# module_SX1262.net
KiCad netlist of a schematic drawn in EAGLE
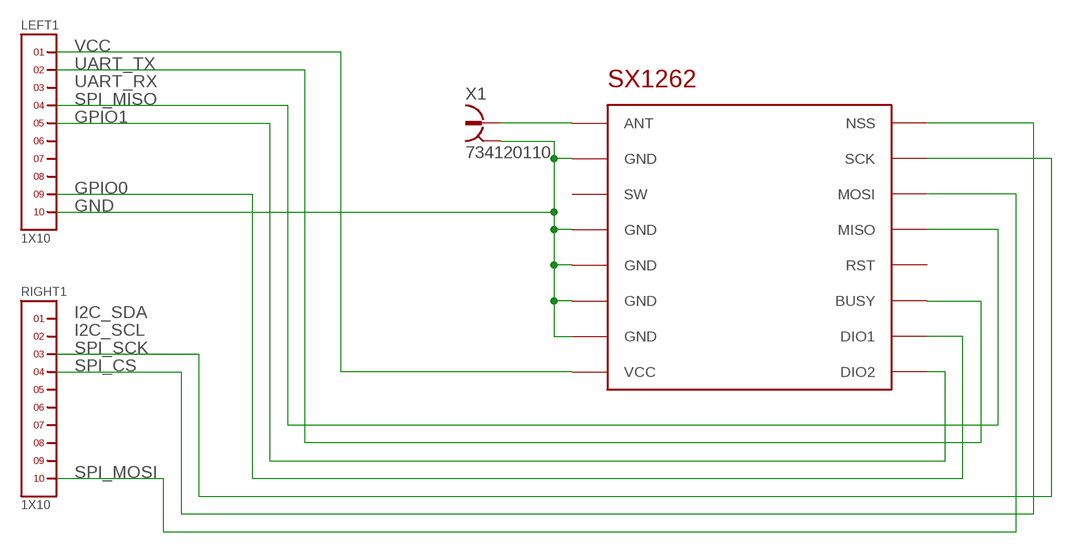
[diagram p0: schematic, sheet 1]

(export (version "E")
  (design (tool "Eeschema 10.0.6"))
  (components
    (comp (ref "LEFT1")
      (value "1X10")
      (footprint "eagle-import:1X10")
      (libsource (lib "eagle-import") (part "1X10"))
    )
    (comp (ref "RIGHT1")
      (value "1X10")
      (footprint "eagle-import:1X10")
      (libsource (lib "eagle-import") (part "1X10"))
    )
    (comp (ref "U$1")
      (value "SX1262")
      (footprint "eagle-import:SX1262")
      (libsource (lib "eagle-import") (part "SX1262"))
    )
    (comp (ref "X1")
      (value "734120110")
      (footprint "eagle-import:734120110")
      (libsource (lib "eagle-import") (part "734120110"))
    )
  )
  (nets
    (net (code "1") (name "Net-(LEFT1-Pad1)") (class "Default")
      (node (ref "LEFT1") (pin "1") (pinfunction "1_1") (pintype "bidirectional"))
      (node (ref "U$1") (pin "VCC") (pinfunction "VCC_VCC") (pintype "bidirectional"))
    )
    (net (code "2") (name "Net-(LEFT1-Pad2)") (class "Default")
      (node (ref "LEFT1") (pin "2") (pinfunction "2_2") (pintype "bidirectional"))
      (node (ref "U$1") (pin "BUSY") (pinfunction "BUSY_BUSY") (pintype "bidirectional"))
    )
    (net (code "3") (name "Net-(LEFT1-Pad4)") (class "Default")
      (node (ref "LEFT1") (pin "4") (pinfunction "4_4") (pintype "bidirectional"))
      (node (ref "U$1") (pin "MISO") (pinfunction "MISO_MISO") (pintype "bidirectional"))
    )
    (net (code "4") (name "Net-(LEFT1-Pad5)") (class "Default")
      (node (ref "LEFT1") (pin "5") (pinfunction "5_5") (pintype "bidirectional"))
      (node (ref "U$1") (pin "DIO2") (pinfunction "DIO2_DIO2") (pintype "bidirectional"))
    )
    (net (code "5") (name "Net-(LEFT1-Pad9)") (class "Default")
      (node (ref "LEFT1") (pin "9") (pinfunction "9_9") (pintype "bidirectional"))
      (node (ref "U$1") (pin "DIO1") (pinfunction "DIO1_DIO1") (pintype "bidirectional"))
    )
    (net (code "6") (name "Net-(LEFT1-Pad10)") (class "Default")
      (node (ref "LEFT1") (pin "10") (pinfunction "10_10") (pintype "bidirectional"))
      (node (ref "U$1") (pin "GND@1") (pinfunction "GND_GND@1") (pintype "bidirectional"))
      (node (ref "U$1") (pin "GND@2") (pinfunction "GND_GND@2") (pintype "bidirectional"))
      (node (ref "U$1") (pin "GND@3") (pinfunction "GND_GND@3") (pintype "bidirectional"))
      (node (ref "U$1") (pin "GND@4") (pinfunction "GND_GND@4") (pintype "bidirectional"))
      (node (ref "U$1") (pin "GND@5") (pinfunction "GND_GND@5") (pintype "bidirectional"))
      (node (ref "X1") (pin "S@1") (pinfunction "2_S@1") (pintype "passive"))
      (node (ref "X1") (pin "S@2") (pinfunction "2_S@2") (pintype "passive"))
      (node (ref "X1") (pin "S@3") (pinfunction "2_S@3") (pintype "passive"))
    )
    (net (code "7") (name "Net-(RIGHT1-Pad3)") (class "Default")
      (node (ref "RIGHT1") (pin "3") (pinfunction "3_3") (pintype "bidirectional"))
      (node (ref "U$1") (pin "SCK") (pinfunction "SCK_SCK") (pintype "bidirectional"))
    )
    (net (code "8") (name "Net-(RIGHT1-Pad4)") (class "Default")
      (node (ref "RIGHT1") (pin "4") (pinfunction "4_4") (pintype "bidirectional"))
      (node (ref "U$1") (pin "NSS") (pinfunction "NSS_NSS") (pintype "bidirectional"))
    )
    (net (code "9") (name "Net-(RIGHT1-Pad10)") (class "Default")
      (node (ref "RIGHT1") (pin "10") (pinfunction "10_10") (pintype "bidirectional"))
      (node (ref "U$1") (pin "MOSI") (pinfunction "MOSI_MOSI") (pintype "bidirectional"))
    )
    (net (code "10") (name "Net-(U$1-PadANT)") (class "Default")
      (node (ref "U$1") (pin "ANT") (pinfunction "ANT_ANT") (pintype "bidirectional"))
      (node (ref "X1") (pin "1") (pinfunction "1_1") (pintype "passive"))
    )
    (net (code "11") (name "unconnected-(LEFT1-Pad3)") (class "Default")
      (node (ref "LEFT1") (pin "3") (pinfunction "3_3") (pintype "bidirectional"))
    )
    (net (code "12") (name "unconnected-(LEFT1-Pad6)") (class "Default")
      (node (ref "LEFT1") (pin "6") (pinfunction "6_6") (pintype "bidirectional"))
    )
    (net (code "13") (name "unconnected-(LEFT1-Pad7)") (class "Default")
      (node (ref "LEFT1") (pin "7") (pinfunction "7_7") (pintype "bidirectional"))
    )
    (net (code "14") (name "unconnected-(LEFT1-Pad8)") (class "Default")
      (node (ref "LEFT1") (pin "8") (pinfunction "8_8") (pintype "bidirectional"))
    )
    (net (code "15") (name "unconnected-(RIGHT1-Pad1)") (class "Default")
      (node (ref "RIGHT1") (pin "1") (pinfunction "1_1") (pintype "bidirectional"))
    )
    (net (code "16") (name "unconnected-(RIGHT1-Pad2)") (class "Default")
      (node (ref "RIGHT1") (pin "2") (pinfunction "2_2") (pintype "bidirectional"))
    )
    (net (code "17") (name "unconnected-(RIGHT1-Pad5)") (class "Default")
      (node (ref "RIGHT1") (pin "5") (pinfunction "5_5") (pintype "bidirectional"))
    )
    (net (code "18") (name "unconnected-(RIGHT1-Pad6)") (class "Default")
      (node (ref "RIGHT1") (pin "6") (pinfunction "6_6") (pintype "bidirectional"))
    )
    (net (code "19") (name "unconnected-(RIGHT1-Pad7)") (class "Default")
      (node (ref "RIGHT1") (pin "7") (pinfunction "7_7") (pintype "bidirectional"))
    )
    (net (code "20") (name "unconnected-(RIGHT1-Pad8)") (class "Default")
      (node (ref "RIGHT1") (pin "8") (pinfunction "8_8") (pintype "bidirectional"))
    )
    (net (code "21") (name "unconnected-(RIGHT1-Pad9)") (class "Default")
      (node (ref "RIGHT1") (pin "9") (pinfunction "9_9") (pintype "bidirectional"))
    )
    (net (code "22") (name "unconnected-(U$1-PadRST)") (class "Default")
      (node (ref "U$1") (pin "RST") (pinfunction "RST_RST") (pintype "bidirectional"))
    )
    (net (code "23") (name "unconnected-(U$1-PadSW)") (class "Default")
      (node (ref "U$1") (pin "SW") (pinfunction "SW_SW") (pintype "bidirectional"))
    )
  )
)
